# Connectors.net
KiCad netlist of a schematic drawn in Altium Designer
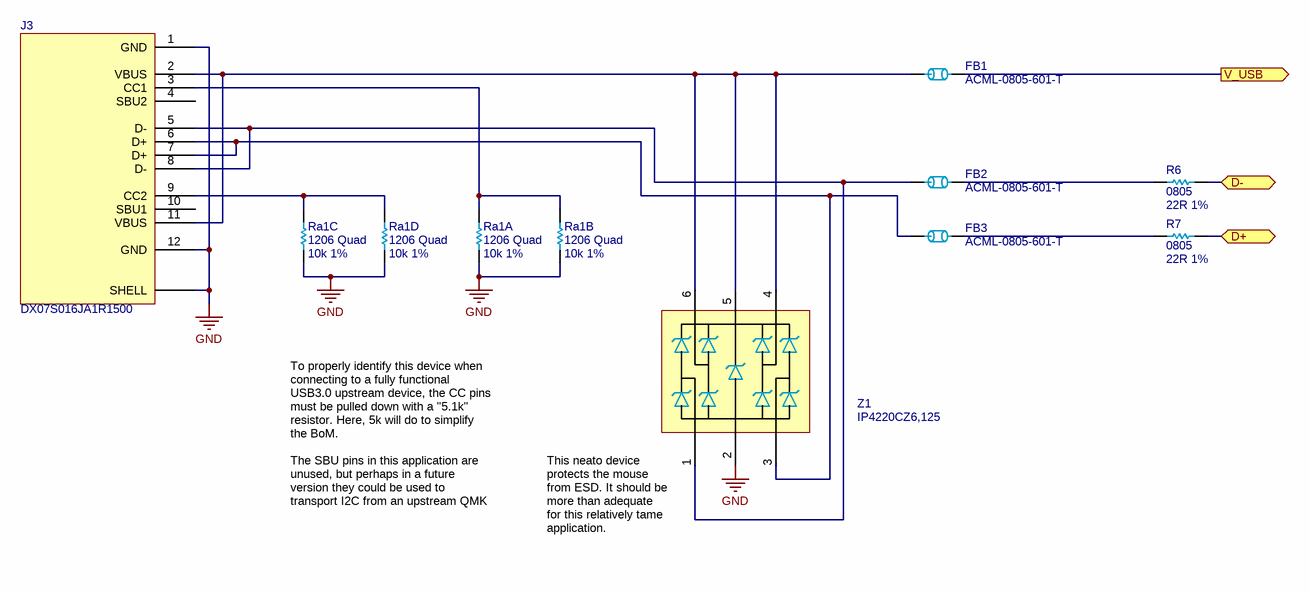
[diagram p0: Connectors.SchDoc]

(export (version "E")
  (design (tool "Eeschema 10.0.6"))
  (components
    (comp (ref "FB1")
      (value "ACML-0805-601-T")
      (footprint "0805")
      (description "FERRITE BEAD 600 OHM 0805 1LN")
      (libsource (lib "Chip_Passives") (part "ACML-0805-601-T"))
    )
    (comp (ref "FB2")
      (value "ACML-0805-601-T")
      (footprint "0805")
      (description "FERRITE BEAD 600 OHM 0805 1LN")
      (libsource (lib "Chip_Passives") (part "ACML-0805-601-T"))
    )
    (comp (ref "FB3")
      (value "ACML-0805-601-T")
      (footprint "0805")
      (description "FERRITE BEAD 600 OHM 0805 1LN")
      (libsource (lib "Chip_Passives") (part "ACML-0805-601-T"))
    )
    (comp (ref "J3")
      (value "DX07S016JA1R1500")
      (footprint "DX07S016JA1R1500")
      (libsource (lib "Connectors") (part "DX07S016JA1R1500"))
    )
    (comp (ref "R6")
      (value "0805")
      (footprint "0805")
      (description "Chip resistor")
      (fields (field (name "ALTIUM_VALUE") "22R 1%"))
      (libsource (lib "Chip_Passives") (part "Res 22R 1% 0805"))
    )
    (comp (ref "R7")
      (value "0805")
      (footprint "0805")
      (description "Chip resistor")
      (fields (field (name "ALTIUM_VALUE") "22R 1%"))
      (libsource (lib "Chip_Passives") (part "Res 22R 1% 0805"))
    )
    (comp (ref "Ra1")
      (value "1206 Quad")
      (footprint "4x 10k 1% - CAC-80P320X160-8M")
      (description "Chip resistor")
      (fields (field (name "ALTIUM_VALUE") "10k 1%"))
      (libsource (lib "Chip_Passives") (part "Quad Res 10k 1% 1206"))
    )
    (comp (ref "Z1")
      (value "IP4220CZ6,125")
      (footprint "PESD3V3S4UD - SOT95P275X110-6N")
      (description "TVS DIODE 5.5V 6TSOP (Low capacitance, USB)")
      (libsource (lib "Diodes") (part "IP4220CZ6,125"))
    )
  )
  (nets
    (net (code "1") (name "/D+") (class "Default")
      (node (ref "R7") (pin "2") (pinfunction "2_2") (pintype "passive"))
    )
    (net (code "2") (name "/D-") (class "Default")
      (node (ref "R6") (pin "2") (pinfunction "2_2") (pintype "passive"))
    )
    (net (code "3") (name "/V_USB") (class "Default")
      (node (ref "FB1") (pin "2") (pinfunction "2_2") (pintype "passive"))
    )
    (net (code "4") (name "GND") (class "Default")
      (node (ref "J3") (pin "1") (pinfunction "GND_1") (pintype "passive"))
      (node (ref "J3") (pin "12") (pinfunction "GND_12") (pintype "passive"))
      (node (ref "J3") (pin "SHELL") (pinfunction "SHELL_SHELL") (pintype "passive"))
      (node (ref "Ra1") (pin "1") (pinfunction "1_1") (pintype "passive"))
      (node (ref "Ra1") (pin "2") (pinfunction "2_2") (pintype "passive"))
      (node (ref "Ra1") (pin "3") (pinfunction "3_3") (pintype "passive"))
      (node (ref "Ra1") (pin "4") (pinfunction "4_4") (pintype "passive"))
      (node (ref "Z1") (pin "2") (pinfunction "2_2") (pintype "passive"))
    )
    (net (code "5") (name "Net-(FB1-Pad1)") (class "Default")
      (node (ref "FB1") (pin "1") (pinfunction "1_1") (pintype "passive"))
      (node (ref "J3") (pin "11") (pinfunction "VBUS_11") (pintype "passive"))
      (node (ref "J3") (pin "2") (pinfunction "VBUS_2") (pintype "passive"))
      (node (ref "Z1") (pin "4") (pinfunction "4_4") (pintype "passive"))
      (node (ref "Z1") (pin "5") (pinfunction "5_5") (pintype "passive"))
      (node (ref "Z1") (pin "6") (pinfunction "6_6") (pintype "passive"))
    )
    (net (code "6") (name "Net-(FB2-Pad1)") (class "Default")
      (node (ref "FB2") (pin "1") (pinfunction "1_1") (pintype "passive"))
      (node (ref "J3") (pin "5") (pinfunction "D-_5") (pintype "passive"))
      (node (ref "J3") (pin "8") (pinfunction "D-_8") (pintype "passive"))
      (node (ref "Z1") (pin "1") (pinfunction "1_1") (pintype "passive"))
    )
    (net (code "7") (name "Net-(FB2-Pad2)") (class "Default")
      (node (ref "FB2") (pin "2") (pinfunction "2_2") (pintype "passive"))
      (node (ref "R6") (pin "1") (pinfunction "1_1") (pintype "passive"))
    )
    (net (code "8") (name "Net-(FB3-Pad1)") (class "Default")
      (node (ref "FB3") (pin "1") (pinfunction "1_1") (pintype "passive"))
      (node (ref "J3") (pin "6") (pinfunction "D+_6") (pintype "passive"))
      (node (ref "J3") (pin "7") (pinfunction "D+_7") (pintype "passive"))
      (node (ref "Z1") (pin "3") (pinfunction "3_3") (pintype "passive"))
    )
    (net (code "9") (name "Net-(FB3-Pad2)") (class "Default")
      (node (ref "FB3") (pin "2") (pinfunction "2_2") (pintype "passive"))
      (node (ref "R7") (pin "1") (pinfunction "1_1") (pintype "passive"))
    )
    (net (code "10") (name "Net-(J3-CC1)") (class "Default")
      (node (ref "J3") (pin "3") (pinfunction "CC1_3") (pintype "passive"))
      (node (ref "Ra1") (pin "7") (pinfunction "7_7") (pintype "passive"))
      (node (ref "Ra1") (pin "8") (pinfunction "8_8") (pintype "passive"))
    )
    (net (code "11") (name "Net-(J3-CC2)") (class "Default")
      (node (ref "J3") (pin "9") (pinfunction "CC2_9") (pintype "passive"))
      (node (ref "Ra1") (pin "5") (pinfunction "5_5") (pintype "passive"))
      (node (ref "Ra1") (pin "6") (pinfunction "6_6") (pintype "passive"))
    )
    (net (code "12") (name "unconnected-(J3-SBU1-Pad10)") (class "Default")
      (node (ref "J3") (pin "10") (pinfunction "SBU1_10") (pintype "passive"))
    )
    (net (code "13") (name "unconnected-(J3-SBU2-Pad4)") (class "Default")
      (node (ref "J3") (pin "4") (pinfunction "SBU2_4") (pintype "passive"))
    )
  )
)
